# lcd.net
KiCad netlist of a schematic drawn in EAGLE
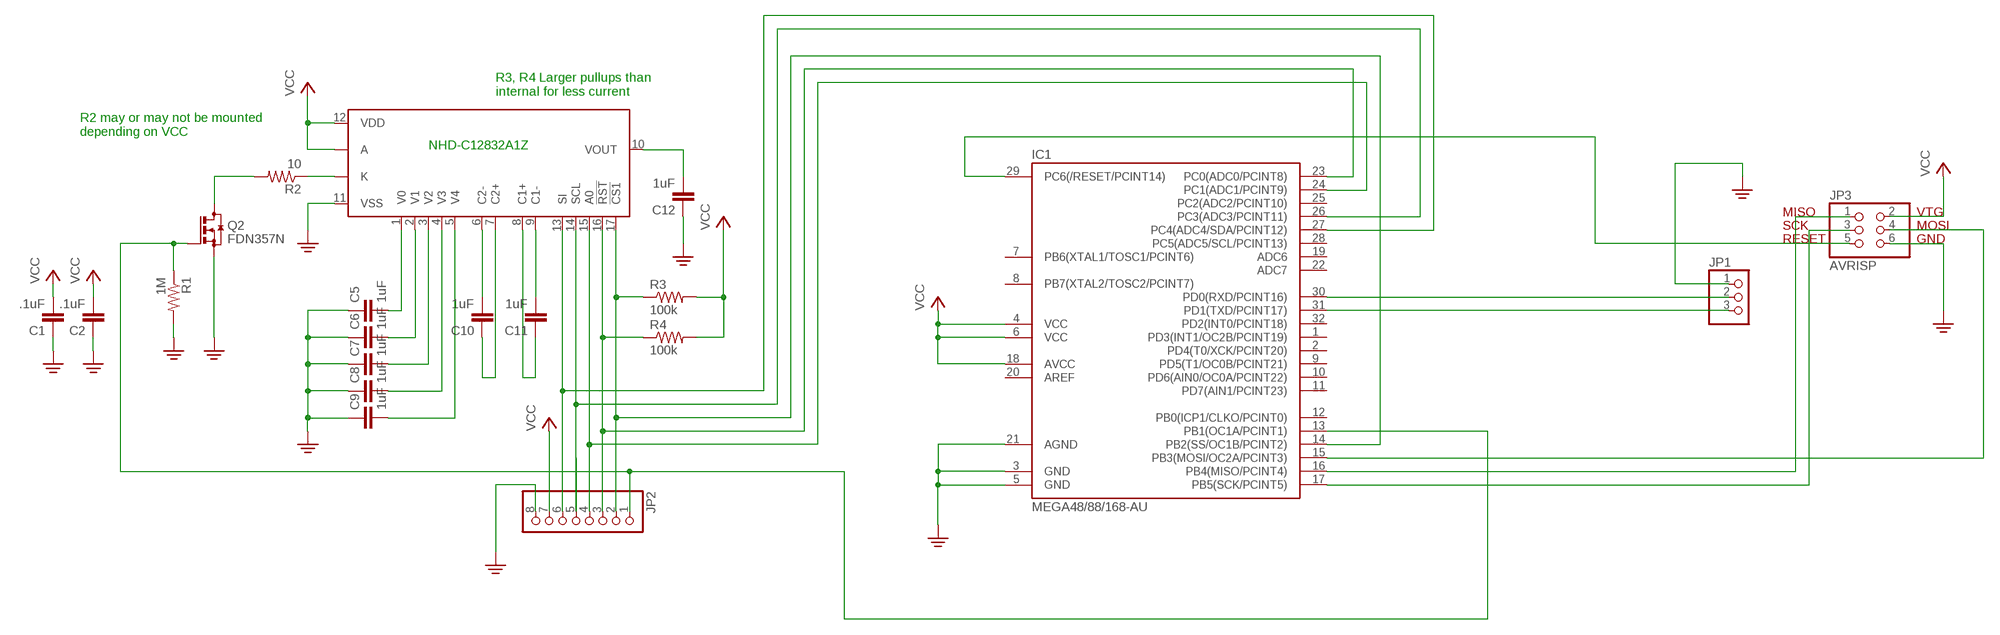
[diagram p0: schematic, sheet 1]

(export (version "E")
  (design (tool "Eeschema 10.0.6"))
  (components
    (comp (ref "C1")
      (value ".1uF")
      (footprint "eagle-import:C0603")
      (libsource (lib "eagle-import") (part "C-EUC0603"))
    )
    (comp (ref "C2")
      (value ".1uF")
      (footprint "eagle-import:C0603")
      (libsource (lib "eagle-import") (part "C-EUC0603"))
    )
    (comp (ref "C5")
      (value "1uF")
      (footprint "eagle-import:C0603")
      (libsource (lib "eagle-import") (part "C-EUC0603"))
    )
    (comp (ref "C6")
      (value "1uF")
      (footprint "eagle-import:C0603")
      (libsource (lib "eagle-import") (part "C-EUC0603"))
    )
    (comp (ref "C7")
      (value "1uF")
      (footprint "eagle-import:C0603")
      (libsource (lib "eagle-import") (part "C-EUC0603"))
    )
    (comp (ref "C8")
      (value "1uF")
      (footprint "eagle-import:C0603")
      (libsource (lib "eagle-import") (part "C-EUC0603"))
    )
    (comp (ref "C9")
      (value "1uF")
      (footprint "eagle-import:C0603")
      (libsource (lib "eagle-import") (part "C-EUC0603"))
    )
    (comp (ref "C10")
      (value "1uF")
      (footprint "eagle-import:C0603")
      (libsource (lib "eagle-import") (part "C-EUC0603"))
    )
    (comp (ref "C11")
      (value "1uF")
      (footprint "eagle-import:C0603")
      (libsource (lib "eagle-import") (part "C-EUC0603"))
    )
    (comp (ref "C12")
      (value "1uF")
      (footprint "eagle-import:C0603")
      (libsource (lib "eagle-import") (part "C-EUC0603"))
    )
    (comp (ref "IC1")
      (value "MEGA48/88/168-AU")
      (footprint "eagle-import:TQFP32-08")
      (libsource (lib "eagle-import") (part "MEGA48/88/168-AU"))
    )
    (comp (ref "JP1")
      (value "PINHD-1X3")
      (footprint "eagle-import:1X03")
      (libsource (lib "eagle-import") (part "PINHD-1X3"))
    )
    (comp (ref "JP2")
      (value "PINHD-1X8")
      (footprint "eagle-import:1X08")
      (libsource (lib "eagle-import") (part "PINHD-1X8"))
    )
    (comp (ref "JP3")
      (value "AVRISP")
      (footprint "eagle-import:2X03")
      (libsource (lib "eagle-import") (part "AVRISP"))
    )
    (comp (ref "Q2")
      (value "FDN357N")
      (footprint "eagle-import:SOT23")
      (libsource (lib "eagle-import") (part "BSS123"))
    )
    (comp (ref "R1")
      (value "1M")
      (footprint "eagle-import:R0603")
      (libsource (lib "eagle-import") (part "R-US_R0603"))
    )
    (comp (ref "R2")
      (value "10")
      (footprint "eagle-import:R0603")
      (libsource (lib "eagle-import") (part "R-US_R0603"))
    )
    (comp (ref "R3")
      (value "100k")
      (footprint "eagle-import:R0603")
      (libsource (lib "eagle-import") (part "R-US_R0603"))
    )
    (comp (ref "R4")
      (value "100k")
      (footprint "eagle-import:R0603")
      (libsource (lib "eagle-import") (part "R-US_R0603"))
    )
    (comp (ref "U$1")
      (value "NHD-C12832A1Z")
      (footprint "eagle-import:NHD-C12832A1Z")
      (libsource (lib "eagle-import") (part "NHD-C12832A1Z"))
    )
  )
  (nets
    (net (code "1") (name "GND") (class "Default")
      (node (ref "C1") (pin "1") (pinfunction "1_1") (pintype "passive"))
      (node (ref "C12") (pin "1") (pinfunction "1_1") (pintype "passive"))
      (node (ref "C2") (pin "1") (pinfunction "1_1") (pintype "passive"))
      (node (ref "C5") (pin "1") (pinfunction "1_1") (pintype "passive"))
      (node (ref "C6") (pin "1") (pinfunction "1_1") (pintype "passive"))
      (node (ref "C7") (pin "1") (pinfunction "1_1") (pintype "passive"))
      (node (ref "C8") (pin "1") (pinfunction "1_1") (pintype "passive"))
      (node (ref "C9") (pin "1") (pinfunction "1_1") (pintype "passive"))
      (node (ref "IC1") (pin "21") (pinfunction "AGND_21") (pintype "power_in"))
      (node (ref "IC1") (pin "3") (pinfunction "GND_3") (pintype "power_in"))
      (node (ref "IC1") (pin "5") (pinfunction "GND_5") (pintype "power_in"))
      (node (ref "JP1") (pin "1") (pinfunction "1_1") (pintype "passive"))
      (node (ref "JP2") (pin "8") (pinfunction "8_8") (pintype "passive"))
      (node (ref "JP3") (pin "6") (pinfunction "6_6") (pintype "passive"))
      (node (ref "Q2") (pin "2") (pinfunction "S_2") (pintype "passive"))
      (node (ref "R1") (pin "2") (pinfunction "2_2") (pintype "passive"))
      (node (ref "U$1") (pin "11") (pinfunction "VSS_11") (pintype "bidirectional"))
    )
    (net (code "2") (name "Net-(IC1-PB1(OC1A{slash}PCINT1))") (class "Default")
      (node (ref "IC1") (pin "13") (pinfunction "PB1(OC1A/PCINT1)_13") (pintype "bidirectional"))
      (node (ref "JP2") (pin "1") (pinfunction "1_1") (pintype "passive"))
      (node (ref "Q2") (pin "1") (pinfunction "G_1") (pintype "passive"))
      (node (ref "R1") (pin "1") (pinfunction "1_1") (pintype "passive"))
    )
    (net (code "3") (name "Net-(IC1-PB2(SS{slash}OC1B{slash}PCINT2))") (class "Default")
      (node (ref "IC1") (pin "14") (pinfunction "PB2(SS/OC1B/PCINT2)_14") (pintype "bidirectional"))
      (node (ref "JP2") (pin "2") (pinfunction "2_2") (pintype "passive"))
      (node (ref "R3") (pin "1") (pinfunction "1_1") (pintype "passive"))
      (node (ref "U$1") (pin "17") (pinfunction "~{CS1}_17") (pintype "bidirectional"))
    )
    (net (code "4") (name "Net-(IC1-PB3(MOSI{slash}OC2A{slash}PCINT3))") (class "Default")
      (node (ref "IC1") (pin "15") (pinfunction "PB3(MOSI/OC2A/PCINT3)_15") (pintype "bidirectional"))
      (node (ref "JP3") (pin "4") (pinfunction "4_4") (pintype "passive"))
    )
    (net (code "5") (name "Net-(IC1-PB4(MISO{slash}PCINT4))") (class "Default")
      (node (ref "IC1") (pin "16") (pinfunction "PB4(MISO/PCINT4)_16") (pintype "bidirectional"))
      (node (ref "JP3") (pin "1") (pinfunction "1_1") (pintype "passive"))
    )
    (net (code "6") (name "Net-(IC1-PB5(SCK{slash}PCINT5))") (class "Default")
      (node (ref "IC1") (pin "17") (pinfunction "PB5(SCK/PCINT5)_17") (pintype "bidirectional"))
      (node (ref "JP3") (pin "3") (pinfunction "3_3") (pintype "passive"))
    )
    (net (code "7") (name "Net-(IC1-PC0(ADC0{slash}PCINT8))") (class "Default")
      (node (ref "IC1") (pin "23") (pinfunction "PC0(ADC0/PCINT8)_23") (pintype "bidirectional"))
      (node (ref "JP2") (pin "3") (pinfunction "3_3") (pintype "passive"))
      (node (ref "R4") (pin "1") (pinfunction "1_1") (pintype "passive"))
      (node (ref "U$1") (pin "16") (pinfunction "~{RST}_16") (pintype "bidirectional"))
    )
    (net (code "8") (name "Net-(IC1-PC1(ADC1{slash}PCINT9))") (class "Default")
      (node (ref "IC1") (pin "24") (pinfunction "PC1(ADC1/PCINT9)_24") (pintype "bidirectional"))
      (node (ref "JP2") (pin "4") (pinfunction "4_4") (pintype "passive"))
      (node (ref "U$1") (pin "15") (pinfunction "A0_15") (pintype "bidirectional"))
    )
    (net (code "9") (name "Net-(IC1-PC3(ADC3{slash}PCINT11))") (class "Default")
      (node (ref "IC1") (pin "26") (pinfunction "PC3(ADC3/PCINT11)_26") (pintype "bidirectional"))
      (node (ref "JP2") (pin "5") (pinfunction "5_5") (pintype "passive"))
      (node (ref "U$1") (pin "14") (pinfunction "SCL_14") (pintype "bidirectional"))
    )
    (net (code "10") (name "Net-(IC1-PC4(ADC4{slash}SDA{slash}PCINT12))") (class "Default")
      (node (ref "IC1") (pin "27") (pinfunction "PC4(ADC4/SDA/PCINT12)_27") (pintype "bidirectional"))
      (node (ref "JP2") (pin "6") (pinfunction "6_6") (pintype "passive"))
      (node (ref "U$1") (pin "13") (pinfunction "SI_13") (pintype "bidirectional"))
    )
    (net (code "11") (name "Net-(IC1-PC6({slash}RESET{slash}PCINT14))") (class "Default")
      (node (ref "IC1") (pin "29") (pinfunction "PC6(/RESET/PCINT14)_29") (pintype "bidirectional"))
      (node (ref "JP3") (pin "5") (pinfunction "5_5") (pintype "passive"))
    )
    (net (code "12") (name "Net-(IC1-PD0(RXD{slash}PCINT16))") (class "Default")
      (node (ref "IC1") (pin "30") (pinfunction "PD0(RXD/PCINT16)_30") (pintype "bidirectional"))
      (node (ref "JP1") (pin "2") (pinfunction "2_2") (pintype "passive"))
    )
    (net (code "13") (name "Net-(IC1-PD1(TXD{slash}PCINT17))") (class "Default")
      (node (ref "IC1") (pin "31") (pinfunction "PD1(TXD/PCINT17)_31") (pintype "bidirectional"))
      (node (ref "JP1") (pin "3") (pinfunction "3_3") (pintype "passive"))
    )
    (net (code "14") (name "Net-(Q2-D)") (class "Default")
      (node (ref "Q2") (pin "3") (pinfunction "D_3") (pintype "passive"))
      (node (ref "R2") (pin "2") (pinfunction "2_2") (pintype "passive"))
    )
    (net (code "15") (name "Net-(R2-Pad1)") (class "Default")
      (node (ref "R2") (pin "1") (pinfunction "1_1") (pintype "passive"))
      (node (ref "U$1") (pin "K") (pinfunction "K_K") (pintype "bidirectional"))
    )
    (net (code "16") (name "Net-(U$1-C1+)") (class "Default")
      (node (ref "C11") (pin "1") (pinfunction "1_1") (pintype "passive"))
      (node (ref "U$1") (pin "8") (pinfunction "C1+_8") (pintype "bidirectional"))
    )
    (net (code "17") (name "Net-(U$1-C1-)") (class "Default")
      (node (ref "C11") (pin "2") (pinfunction "2_2") (pintype "passive"))
      (node (ref "U$1") (pin "9") (pinfunction "C1-_9") (pintype "bidirectional"))
    )
    (net (code "18") (name "Net-(U$1-C2+)") (class "Default")
      (node (ref "C10") (pin "1") (pinfunction "1_1") (pintype "passive"))
      (node (ref "U$1") (pin "7") (pinfunction "C2+_7") (pintype "bidirectional"))
    )
    (net (code "19") (name "Net-(U$1-C2-)") (class "Default")
      (node (ref "C10") (pin "2") (pinfunction "2_2") (pintype "passive"))
      (node (ref "U$1") (pin "6") (pinfunction "C2-_6") (pintype "bidirectional"))
    )
    (net (code "20") (name "Net-(U$1-V0)") (class "Default")
      (node (ref "C5") (pin "2") (pinfunction "2_2") (pintype "passive"))
      (node (ref "U$1") (pin "1") (pinfunction "V0_1") (pintype "bidirectional"))
    )
    (net (code "21") (name "Net-(U$1-V1)") (class "Default")
      (node (ref "C6") (pin "2") (pinfunction "2_2") (pintype "passive"))
      (node (ref "U$1") (pin "2") (pinfunction "V1_2") (pintype "bidirectional"))
    )
    (net (code "22") (name "Net-(U$1-V2)") (class "Default")
      (node (ref "C7") (pin "2") (pinfunction "2_2") (pintype "passive"))
      (node (ref "U$1") (pin "3") (pinfunction "V2_3") (pintype "bidirectional"))
    )
    (net (code "23") (name "Net-(U$1-V3)") (class "Default")
      (node (ref "C8") (pin "2") (pinfunction "2_2") (pintype "passive"))
      (node (ref "U$1") (pin "4") (pinfunction "V3_4") (pintype "bidirectional"))
    )
    (net (code "24") (name "Net-(U$1-V4)") (class "Default")
      (node (ref "C9") (pin "2") (pinfunction "2_2") (pintype "passive"))
      (node (ref "U$1") (pin "5") (pinfunction "V4_5") (pintype "bidirectional"))
    )
    (net (code "25") (name "Net-(U$1-VOUT)") (class "Default")
      (node (ref "C12") (pin "2") (pinfunction "2_2") (pintype "passive"))
      (node (ref "U$1") (pin "10") (pinfunction "VOUT_10") (pintype "bidirectional"))
    )
    (net (code "26") (name "VCC") (class "Default")
      (node (ref "C1") (pin "2") (pinfunction "2_2") (pintype "passive"))
      (node (ref "C2") (pin "2") (pinfunction "2_2") (pintype "passive"))
      (node (ref "IC1") (pin "18") (pinfunction "AVCC_18") (pintype "passive"))
      (node (ref "IC1") (pin "4") (pinfunction "VCC_4") (pintype "power_in"))
      (node (ref "IC1") (pin "6") (pinfunction "VCC_6") (pintype "power_in"))
      (node (ref "JP2") (pin "7") (pinfunction "7_7") (pintype "passive"))
      (node (ref "JP3") (pin "2") (pinfunction "2_2") (pintype "passive"))
      (node (ref "R3") (pin "2") (pinfunction "2_2") (pintype "passive"))
      (node (ref "R4") (pin "2") (pinfunction "2_2") (pintype "passive"))
      (node (ref "U$1") (pin "12") (pinfunction "VDD_12") (pintype "bidirectional"))
      (node (ref "U$1") (pin "A") (pinfunction "A_A") (pintype "bidirectional"))
    )
    (net (code "27") (name "unconnected-(IC1-ADC6-Pad19)") (class "Default")
      (node (ref "IC1") (pin "19") (pinfunction "ADC6_19") (pintype "passive"))
    )
    (net (code "28") (name "unconnected-(IC1-ADC7-Pad22)") (class "Default")
      (node (ref "IC1") (pin "22") (pinfunction "ADC7_22") (pintype "passive"))
    )
    (net (code "29") (name "unconnected-(IC1-AREF-Pad20)") (class "Default")
      (node (ref "IC1") (pin "20") (pinfunction "AREF_20") (pintype "passive"))
    )
    (net (code "30") (name "unconnected-(IC1-PB0(ICP1{slash}CLKO{slash}PCINT0)-Pad12)") (class "Default")
      (node (ref "IC1") (pin "12") (pinfunction "PB0(ICP1/CLKO/PCINT0)_12") (pintype "bidirectional"))
    )
    (net (code "31") (name "unconnected-(IC1-PB6(XTAL1{slash}TOSC1{slash}PCINT6)-Pad7)") (class "Default")
      (node (ref "IC1") (pin "7") (pinfunction "PB6(XTAL1/TOSC1/PCINT6)_7") (pintype "bidirectional"))
    )
    (net (code "32") (name "unconnected-(IC1-PB7(XTAL2{slash}TOSC2{slash}PCINT7)-Pad8)") (class "Default")
      (node (ref "IC1") (pin "8") (pinfunction "PB7(XTAL2/TOSC2/PCINT7)_8") (pintype "bidirectional"))
    )
    (net (code "33") (name "unconnected-(IC1-PC2(ADC2{slash}PCINT10)-Pad25)") (class "Default")
      (node (ref "IC1") (pin "25") (pinfunction "PC2(ADC2/PCINT10)_25") (pintype "bidirectional"))
    )
    (net (code "34") (name "unconnected-(IC1-PC5(ADC5{slash}SCL{slash}PCINT13)-Pad28)") (class "Default")
      (node (ref "IC1") (pin "28") (pinfunction "PC5(ADC5/SCL/PCINT13)_28") (pintype "bidirectional"))
    )
    (net (code "35") (name "unconnected-(IC1-PD2(INT0{slash}PCINT18)-Pad32)") (class "Default")
      (node (ref "IC1") (pin "32") (pinfunction "PD2(INT0/PCINT18)_32") (pintype "bidirectional"))
    )
    (net (code "36") (name "unconnected-(IC1-PD3(INT1{slash}OC2B{slash}PCINT19)-Pad1)") (class "Default")
      (node (ref "IC1") (pin "1") (pinfunction "PD3(INT1/OC2B/PCINT19)_1") (pintype "bidirectional"))
    )
    (net (code "37") (name "unconnected-(IC1-PD4(T0{slash}XCK{slash}PCINT20)-Pad2)") (class "Default")
      (node (ref "IC1") (pin "2") (pinfunction "PD4(T0/XCK/PCINT20)_2") (pintype "bidirectional"))
    )
    (net (code "38") (name "unconnected-(IC1-PD5(T1{slash}OC0B{slash}PCINT21)-Pad9)") (class "Default")
      (node (ref "IC1") (pin "9") (pinfunction "PD5(T1/OC0B/PCINT21)_9") (pintype "bidirectional"))
    )
    (net (code "39") (name "unconnected-(IC1-PD6(AIN0{slash}OC0A{slash}PCINT22)-Pad10)") (class "Default")
      (node (ref "IC1") (pin "10") (pinfunction "PD6(AIN0/OC0A/PCINT22)_10") (pintype "bidirectional"))
    )
    (net (code "40") (name "unconnected-(IC1-PD7(AIN1{slash}PCINT23)-Pad11)") (class "Default")
      (node (ref "IC1") (pin "11") (pinfunction "PD7(AIN1/PCINT23)_11") (pintype "bidirectional"))
    )
  )
)
